# ADC.net
KiCad netlist of a schematic drawn in Altium Designer
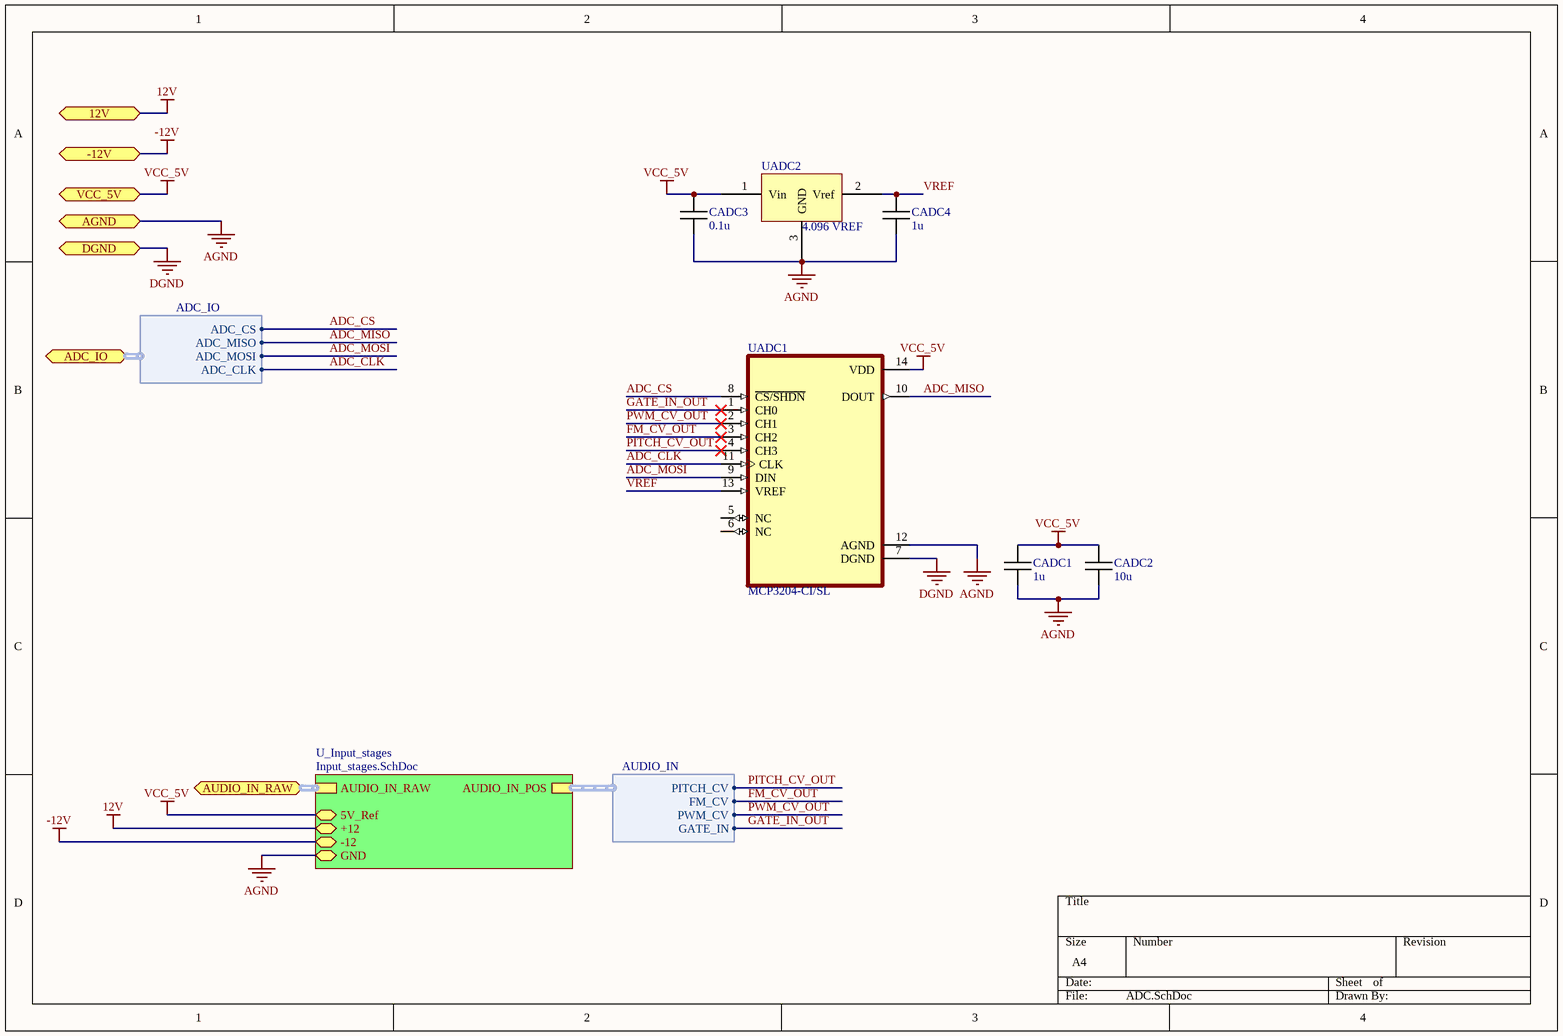
[diagram p0: ADC.SchDoc]

(export (version "E")
  (design (tool "Eeschema 10.0.6"))
  (components
    (comp (ref "CADC1")
      (value "1u")
      (footprint "C 0603 / 1608")
      (libsource (lib "Standard") (part "Capacitor"))
    )
    (comp (ref "CADC2")
      (value "10u")
      (footprint "C 0603 / 1608")
      (libsource (lib "Standard") (part "Capacitor"))
    )
    (comp (ref "CADC3")
      (value "0.1u")
      (footprint "C 0603 / 1608")
      (libsource (lib "Standard") (part "Capacitor"))
    )
    (comp (ref "CADC4")
      (value "1u")
      (footprint "C 0603 / 1608")
      (libsource (lib "Standard") (part "Capacitor"))
    )
    (comp (ref "UADC1")
      (value "MCP3204-CI/SL")
      (footprint "SOIC-14")
      (description "12 Bit Analog to Digital Converter 2, 4 Input 1 SAR 14-SOIC")
      (fields (field (name "MF") "Microchip"))
      (libsource (lib "IC") (part "MCP3204-CI/SL"))
    )
    (comp (ref "UADC2")
      (value "4.096 VREF")
      (footprint "SOT-23-3")
      (description "4.096 Voltage reference")
      (libsource (lib "IC") (part "MCP1541"))
    )
  )
  (nets
    (net (code "5") (name "/ADC_CLK") (class "Default")
      (node (ref "UADC1") (pin "11") (pinfunction "CLK_11") (pintype "input"))
    )
    (net (code "6") (name "/ADC_CS") (class "Default")
      (node (ref "UADC1") (pin "8") (pinfunction "~{CS/SHDN}_8") (pintype "input"))
    )
    (net (code "7") (name "/ADC_MISO") (class "Default")
      (node (ref "UADC1") (pin "10") (pinfunction "DOUT_10") (pintype "output"))
    )
    (net (code "8") (name "/ADC_MOSI") (class "Default")
      (node (ref "UADC1") (pin "9") (pinfunction "DIN_9") (pintype "input"))
    )
    (net (code "10") (name "/FM_CV_OUT") (class "Default")
      (node (ref "UADC1") (pin "3") (pinfunction "CH2_3") (pintype "input"))
    )
    (net (code "11") (name "/GATE_IN_OUT") (class "Default")
      (node (ref "UADC1") (pin "1") (pinfunction "CH0_1") (pintype "input"))
    )
    (net (code "12") (name "/PITCH_CV_OUT") (class "Default")
      (node (ref "UADC1") (pin "4") (pinfunction "CH3_4") (pintype "input"))
    )
    (net (code "13") (name "/PWM_CV_OUT") (class "Default")
      (node (ref "UADC1") (pin "2") (pinfunction "CH1_2") (pintype "input"))
    )
    (net (code "14") (name "/VREF") (class "Default")
      (node (ref "CADC4") (pin "1") (pinfunction "1_1") (pintype "passive"))
      (node (ref "UADC1") (pin "13") (pinfunction "VREF_13") (pintype "input"))
      (node (ref "UADC2") (pin "2") (pinfunction "Vref_2") (pintype "passive"))
    )
    (net (code "18") (name "AGND") (class "Default")
      (node (ref "CADC1") (pin "2") (pinfunction "1_2") (pintype "passive"))
      (node (ref "CADC2") (pin "2") (pinfunction "1_2") (pintype "passive"))
      (node (ref "CADC3") (pin "2") (pinfunction "1_2") (pintype "passive"))
      (node (ref "CADC4") (pin "2") (pinfunction "1_2") (pintype "passive"))
      (node (ref "UADC1") (pin "12") (pinfunction "AGND_12") (pintype "power_in"))
      (node (ref "UADC2") (pin "3") (pinfunction "GND_3") (pintype "passive"))
    )
    (net (code "19") (name "DGND") (class "Default")
      (node (ref "UADC1") (pin "7") (pinfunction "DGND_7") (pintype "power_in"))
    )
    (net (code "20") (name "VCC_5V") (class "Default")
      (node (ref "CADC1") (pin "1") (pinfunction "1_1") (pintype "passive"))
      (node (ref "CADC2") (pin "1") (pinfunction "1_1") (pintype "passive"))
      (node (ref "CADC3") (pin "1") (pinfunction "1_1") (pintype "passive"))
      (node (ref "UADC1") (pin "14") (pinfunction "VDD_14") (pintype "power_in"))
      (node (ref "UADC2") (pin "1") (pinfunction "Vin_1") (pintype "passive"))
    )
    (net (code "21") (name "unconnected-(UADC1-NC-Pad5)") (class "Default")
      (node (ref "UADC1") (pin "5") (pinfunction "NC_5") (pintype "bidirectional"))
    )
    (net (code "22") (name "unconnected-(UADC1-NC-Pad6)") (class "Default")
      (node (ref "UADC1") (pin "6") (pinfunction "NC_6") (pintype "bidirectional"))
    )
  )
)
